# rc_servo.net
KiCad netlist of a schematic drawn in EAGLE
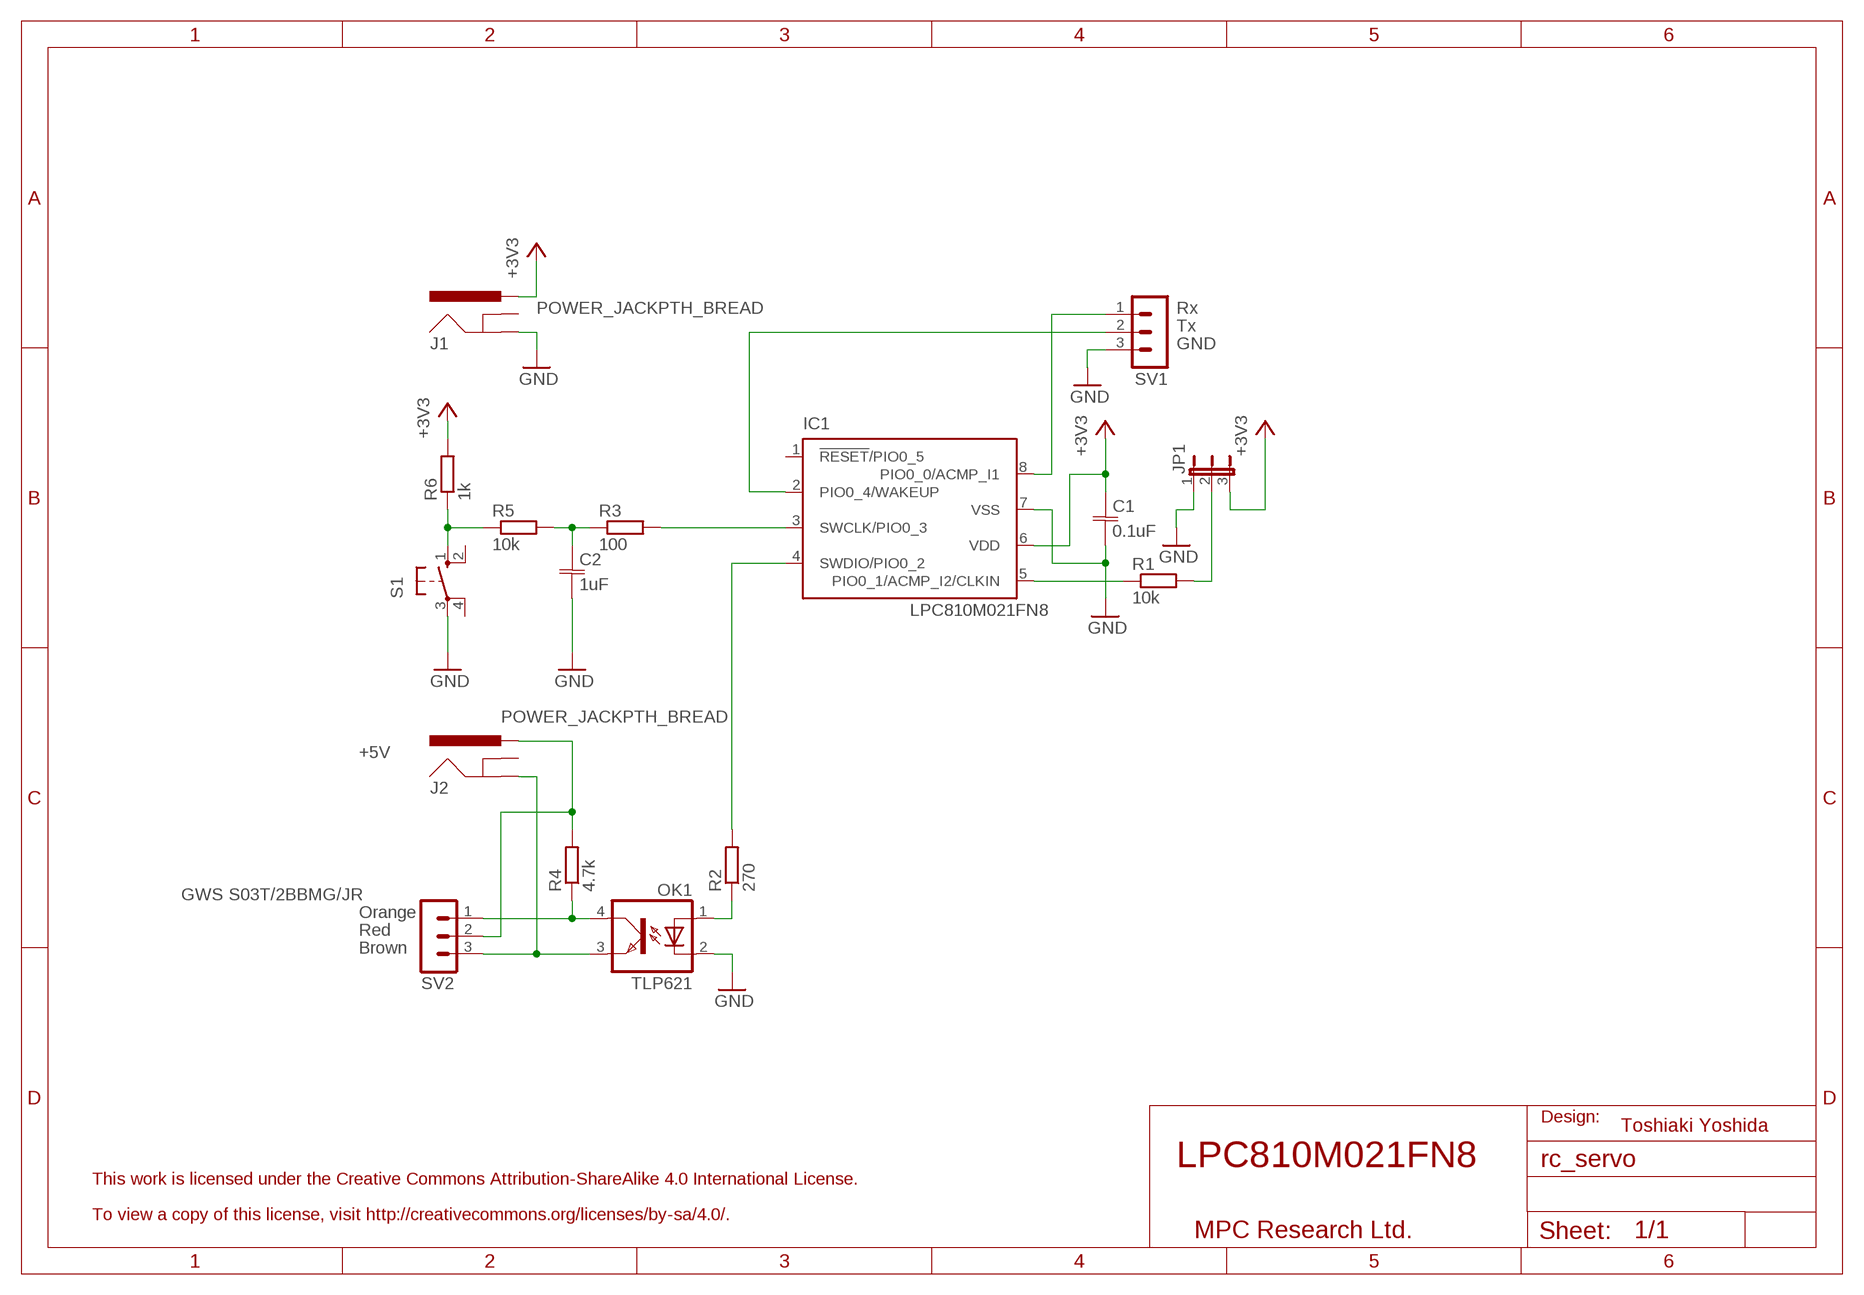
[diagram p0: schematic, sheet 1]

(export (version "E")
  (design (tool "Eeschema 10.0.6"))
  (components
    (comp (ref "C1")
      (value "0.1uF")
      (footprint "eagle-import:C050-024X044")
      (libsource (lib "eagle-import") (part "C-JIS050-024X044"))
    )
    (comp (ref "C2")
      (value "1uF")
      (footprint "eagle-import:C050-024X044")
      (libsource (lib "eagle-import") (part "C-JIS050-024X044"))
    )
    (comp (ref "IC1")
      (value "LPC810M021FN8")
      (footprint "eagle-import:DIL08")
      (libsource (lib "eagle-import") (part "LPC810M021FN8"))
    )
    (comp (ref "J1")
      (value "POWER_JACKPTH_BREAD")
      (footprint "eagle-import:POWER_JACK_PTH_BREAD")
      (libsource (lib "eagle-import") (part "POWER_JACKPTH_BREAD"))
    )
    (comp (ref "J2")
      (value "POWER_JACKPTH_BREAD")
      (footprint "eagle-import:POWER_JACK_PTH_BREAD")
      (libsource (lib "eagle-import") (part "POWER_JACKPTH_BREAD"))
    )
    (comp (ref "JP1")
      (value "JP2E")
      (footprint "eagle-import:JP2")
      (libsource (lib "eagle-import") (part "JP2E"))
    )
    (comp (ref "OK1")
      (value "TLP621")
      (footprint "eagle-import:DIL04")
      (fields (field (name "MPN") "PC817X4J000F"))
      (libsource (lib "eagle-import") (part "PC817"))
    )
    (comp (ref "R1")
      (value "10k")
      (footprint "eagle-import:0207_10")
      (libsource (lib "eagle-import") (part "R-EU_0207/10"))
    )
    (comp (ref "R2")
      (value "270")
      (footprint "eagle-import:0207_10")
      (libsource (lib "eagle-import") (part "R-EU_0207/10"))
    )
    (comp (ref "R3")
      (value "100")
      (footprint "eagle-import:0207_10")
      (libsource (lib "eagle-import") (part "R-EU_0207/10"))
    )
    (comp (ref "R4")
      (value "4.7k")
      (footprint "eagle-import:0207_10")
      (libsource (lib "eagle-import") (part "R-EU_0207/10"))
    )
    (comp (ref "R5")
      (value "10k")
      (footprint "eagle-import:0207_10")
      (libsource (lib "eagle-import") (part "R-EU_0207/10"))
    )
    (comp (ref "R6")
      (value "1k")
      (footprint "eagle-import:0207_10")
      (libsource (lib "eagle-import") (part "R-EU_0207/10"))
    )
    (comp (ref "S1")
      (value "10-XX")
      (footprint "eagle-import:B3F-10XX")
      (fields (field (name "MPN") "B3F-1000"))
      (libsource (lib "eagle-import") (part "10-XX"))
    )
    (comp (ref "SV1")
      (value "MA03-1")
      (footprint "eagle-import:MA03-1")
      (libsource (lib "eagle-import") (part "MA03-1"))
    )
    (comp (ref "SV2")
      (value "MA03-1")
      (footprint "eagle-import:MA03-1")
      (libsource (lib "eagle-import") (part "MA03-1"))
    )
  )
  (nets
    (net (code "1") (name "+3V3") (class "Default")
      (node (ref "C1") (pin "1") (pinfunction "1_1") (pintype "passive"))
      (node (ref "IC1") (pin "6") (pinfunction "VDD_6") (pintype "power_in"))
      (node (ref "J1") (pin "PWR") (pinfunction "PWR_PWR") (pintype "bidirectional"))
      (node (ref "JP1") (pin "3") (pinfunction "3_3") (pintype "passive"))
      (node (ref "R6") (pin "2") (pinfunction "2_2") (pintype "passive"))
    )
    (net (code "2") (name "GND") (class "Default")
      (node (ref "C1") (pin "2") (pinfunction "2_2") (pintype "passive"))
      (node (ref "C2") (pin "2") (pinfunction "2_2") (pintype "passive"))
      (node (ref "IC1") (pin "7") (pinfunction "VSS_7") (pintype "power_in"))
      (node (ref "J1") (pin "GND") (pinfunction "GND_GND") (pintype "bidirectional"))
      (node (ref "JP1") (pin "1") (pinfunction "1_1") (pintype "passive"))
      (node (ref "OK1") (pin "2") (pinfunction "C_2") (pintype "passive"))
      (node (ref "S1") (pin "3") (pinfunction "P_3") (pintype "passive"))
      (node (ref "SV1") (pin "3") (pinfunction "3_3") (pintype "passive"))
    )
    (net (code "3") (name "Net-(C2-Pad1)") (class "Default")
      (node (ref "C2") (pin "1") (pinfunction "1_1") (pintype "passive"))
      (node (ref "R3") (pin "1") (pinfunction "1_1") (pintype "passive"))
      (node (ref "R5") (pin "2") (pinfunction "2_2") (pintype "passive"))
    )
    (net (code "4") (name "Net-(IC1-PIO0_0{slash}ACMP_I1)") (class "Default")
      (node (ref "IC1") (pin "8") (pinfunction "PIO0_0/ACMP_I1_8") (pintype "bidirectional"))
      (node (ref "SV1") (pin "1") (pinfunction "1_1") (pintype "passive"))
    )
    (net (code "5") (name "Net-(IC1-PIO0_1{slash}ACMP_I2{slash}CLKIN)") (class "Default")
      (node (ref "IC1") (pin "5") (pinfunction "PIO0_1/ACMP_I2/CLKIN_5") (pintype "bidirectional"))
      (node (ref "R1") (pin "1") (pinfunction "1_1") (pintype "passive"))
    )
    (net (code "6") (name "Net-(IC1-PIO0_4{slash}WAKEUP)") (class "Default")
      (node (ref "IC1") (pin "2") (pinfunction "PIO0_4/WAKEUP_2") (pintype "bidirectional"))
      (node (ref "SV1") (pin "2") (pinfunction "2_2") (pintype "passive"))
    )
    (net (code "7") (name "Net-(IC1-SWCLK{slash}PIO0_3)") (class "Default")
      (node (ref "IC1") (pin "3") (pinfunction "SWCLK/PIO0_3_3") (pintype "bidirectional"))
      (node (ref "R3") (pin "2") (pinfunction "2_2") (pintype "passive"))
    )
    (net (code "8") (name "Net-(IC1-SWDIO{slash}PIO0_2)") (class "Default")
      (node (ref "IC1") (pin "4") (pinfunction "SWDIO/PIO0_2_4") (pintype "bidirectional"))
      (node (ref "R2") (pin "2") (pinfunction "2_2") (pintype "passive"))
    )
    (net (code "9") (name "Net-(J2-PadPWR)") (class "Default")
      (node (ref "J2") (pin "PWR") (pinfunction "PWR_PWR") (pintype "bidirectional"))
      (node (ref "R4") (pin "2") (pinfunction "2_2") (pintype "passive"))
      (node (ref "SV2") (pin "2") (pinfunction "2_2") (pintype "passive"))
    )
    (net (code "10") (name "Net-(JP1-Pad2)") (class "Default")
      (node (ref "JP1") (pin "2") (pinfunction "2_2") (pintype "passive"))
      (node (ref "R1") (pin "2") (pinfunction "2_2") (pintype "passive"))
    )
    (net (code "11") (name "Net-(OK1-A)") (class "Default")
      (node (ref "OK1") (pin "1") (pinfunction "A_1") (pintype "passive"))
      (node (ref "R2") (pin "1") (pinfunction "1_1") (pintype "passive"))
    )
    (net (code "12") (name "Net-(OK1-COL)") (class "Default")
      (node (ref "OK1") (pin "4") (pinfunction "COL_4") (pintype "passive"))
      (node (ref "R4") (pin "1") (pinfunction "1_1") (pintype "passive"))
      (node (ref "SV2") (pin "1") (pinfunction "1_1") (pintype "passive"))
    )
    (net (code "13") (name "Net-(OK1-EMIT)") (class "Default")
      (node (ref "J2") (pin "GND") (pinfunction "GND_GND") (pintype "bidirectional"))
      (node (ref "OK1") (pin "3") (pinfunction "EMIT_3") (pintype "passive"))
      (node (ref "SV2") (pin "3") (pinfunction "3_3") (pintype "passive"))
    )
    (net (code "14") (name "Net-(S1-S)") (class "Default")
      (node (ref "R5") (pin "1") (pinfunction "1_1") (pintype "passive"))
      (node (ref "R6") (pin "1") (pinfunction "1_1") (pintype "passive"))
      (node (ref "S1") (pin "1") (pinfunction "S_1") (pintype "passive"))
    )
    (net (code "15") (name "unconnected-(IC1-~{RESET}{slash}PIO0_5-Pad1)") (class "Default")
      (node (ref "IC1") (pin "1") (pinfunction "~{RESET}/PIO0_5_1") (pintype "bidirectional"))
    )
    (net (code "16") (name "unconnected-(J1-PadGNDBREAK)") (class "Default")
      (node (ref "J1") (pin "GNDBREAK") (pinfunction "GNDBREAK_GNDBREAK") (pintype "bidirectional"))
    )
    (net (code "17") (name "unconnected-(J2-PadGNDBREAK)") (class "Default")
      (node (ref "J2") (pin "GNDBREAK") (pinfunction "GNDBREAK_GNDBREAK") (pintype "bidirectional"))
    )
    (net (code "18") (name "unconnected-(S1-P1-Pad4)") (class "Default")
      (node (ref "S1") (pin "4") (pinfunction "P1_4") (pintype "passive"))
    )
    (net (code "19") (name "unconnected-(S1-S1-Pad2)") (class "Default")
      (node (ref "S1") (pin "2") (pinfunction "S1_2") (pintype "passive"))
    )
  )
)
